# schematic.net
KiCad netlist of a schematic drawn in EAGLE
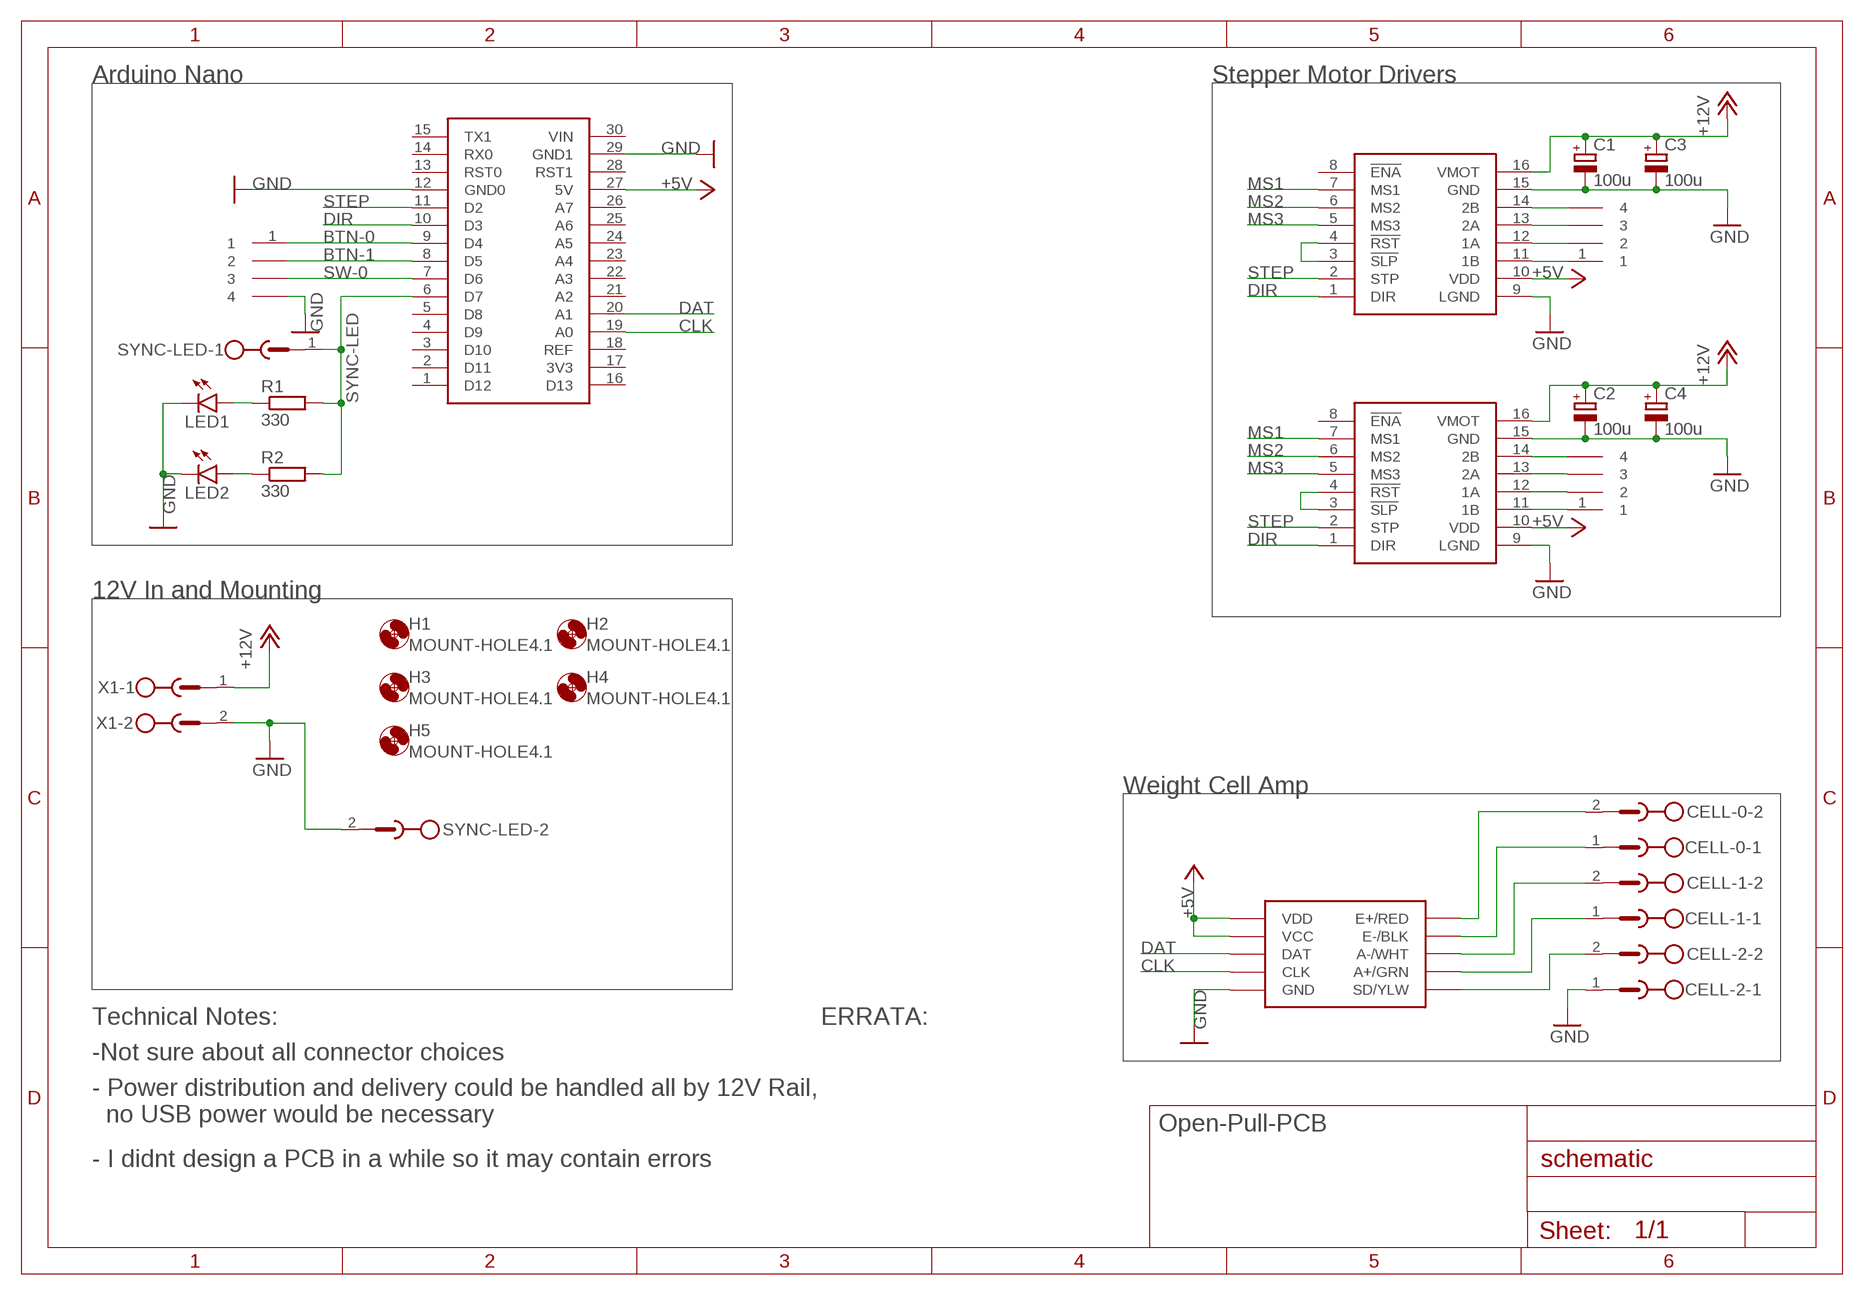
[diagram p0: schematic, sheet 1]

(export (version "E")
  (design (tool "Eeschema 10.0.6"))
  (components
    (comp (ref "C1")
      (value "100u")
      (footprint "eagle-import:3.5MM-CAP")
      (libsource (lib "eagle-import") (part "CPOL"))
    )
    (comp (ref "C2")
      (value "100u")
      (footprint "eagle-import:3.5MM-CAP")
      (libsource (lib "eagle-import") (part "CPOL"))
    )
    (comp (ref "C3")
      (value "100u")
      (footprint "eagle-import:CAPAE830X1050")
      (libsource (lib "eagle-import") (part "CPOLSMD-CAP"))
    )
    (comp (ref "C4")
      (value "100u")
      (footprint "eagle-import:CAPAE830X1050")
      (libsource (lib "eagle-import") (part "CPOLSMD-CAP"))
    )
    (comp (ref "CELL-0")
      (value "MSTBV2")
      (footprint "eagle-import:MSTBV2")
      (libsource (lib "eagle-import") (part "MSTBV2"))
    )
    (comp (ref "CELL-1")
      (value "MSTBV2")
      (footprint "eagle-import:MSTBV2")
      (libsource (lib "eagle-import") (part "MSTBV2"))
    )
    (comp (ref "CELL-2")
      (value "MSTBV2")
      (footprint "eagle-import:MSTBV2")
      (libsource (lib "eagle-import") (part "MSTBV2"))
    )
    (comp (ref "CON1")
      (value "CON-4GENERIC")
      (footprint "eagle-import:HDRV4W64P254_1X4_1016X508X838B")
      (libsource (lib "eagle-import") (part "CON-4GENERIC"))
    )
    (comp (ref "CON2")
      (value "CON-4GENERIC")
      (footprint "eagle-import:HDRV4W64P254_1X4_1016X508X838B")
      (libsource (lib "eagle-import") (part "CON-4GENERIC"))
    )
    (comp (ref "CON3")
      (value "CON-4GENERIC")
      (footprint "eagle-import:HDRV4W64P254_1X4_1016X508X838B")
      (libsource (lib "eagle-import") (part "CON-4GENERIC"))
    )
    (comp (ref "DRIVER1")
      (value "A4988-MODULE")
      (footprint "eagle-import:POLULU-A4988")
      (libsource (lib "eagle-import") (part "A4988-MODULE"))
    )
    (comp (ref "DRIVER2")
      (value "A4988-MODULE")
      (footprint "eagle-import:POLULU-A4988")
      (libsource (lib "eagle-import") (part "A4988-MODULE"))
    )
    (comp (ref "H1")
      (value "MOUNT-HOLE4.1")
      (footprint "eagle-import:4,1")
      (libsource (lib "eagle-import") (part "MOUNT-HOLE4.1"))
    )
    (comp (ref "H2")
      (value "MOUNT-HOLE4.1")
      (footprint "eagle-import:4,1")
      (libsource (lib "eagle-import") (part "MOUNT-HOLE4.1"))
    )
    (comp (ref "H3")
      (value "MOUNT-HOLE4.1")
      (footprint "eagle-import:4,1")
      (libsource (lib "eagle-import") (part "MOUNT-HOLE4.1"))
    )
    (comp (ref "H4")
      (value "MOUNT-HOLE4.1")
      (footprint "eagle-import:4,1")
      (libsource (lib "eagle-import") (part "MOUNT-HOLE4.1"))
    )
    (comp (ref "H5")
      (value "MOUNT-HOLE4.1")
      (footprint "eagle-import:4,1")
      (libsource (lib "eagle-import") (part "MOUNT-HOLE4.1"))
    )
    (comp (ref "LED1")
      (value "LEDCHIP-LED0805")
      (footprint "eagle-import:CHIP-LED0805")
      (libsource (lib "eagle-import") (part "LEDCHIP-LED0805"))
    )
    (comp (ref "LED2")
      (value "LED3MM")
      (footprint "eagle-import:LED3MM")
      (libsource (lib "eagle-import") (part "LED3MM"))
    )
    (comp (ref "MODULE1")
      (value "HX711-MODULE")
      (footprint "eagle-import:SPARKFUN-HX711")
      (libsource (lib "eagle-import") (part "HX711-MODULE"))
    )
    (comp (ref "NANO1")
      (value "ARDUINO-NANO")
      (footprint "eagle-import:ARDUINO-NANO")
      (libsource (lib "eagle-import") (part "ARDUINO-NANO"))
    )
    (comp (ref "R1")
      (value "330")
      (footprint "eagle-import:R0805")
      (libsource (lib "eagle-import") (part "R-EU_R0805"))
    )
    (comp (ref "R2")
      (value "330")
      (footprint "eagle-import:0207_2V")
      (libsource (lib "eagle-import") (part "R-EU_0207/2V"))
    )
    (comp (ref "SYNC-LED")
      (value "MSTBV2")
      (footprint "eagle-import:MSTBV2")
      (libsource (lib "eagle-import") (part "MSTBV2"))
    )
    (comp (ref "X1")
      (value "MSTBV2")
      (footprint "eagle-import:MSTBV2")
      (libsource (lib "eagle-import") (part "MSTBV2"))
    )
  )
  (nets
    (net (code "1") (name "+5V") (class "Default")
      (node (ref "DRIVER1") (pin "10") (pinfunction "VDD_10") (pintype "power_in"))
      (node (ref "DRIVER2") (pin "10") (pinfunction "VDD_10") (pintype "power_in"))
      (node (ref "MODULE1") (pin "VCC") (pinfunction "VCC_VCC") (pintype "power_in"))
      (node (ref "MODULE1") (pin "VDD") (pinfunction "VDD_VDD") (pintype "power_in"))
      (node (ref "NANO1") (pin "27") (pinfunction "5V_27") (pintype "power_in"))
    )
    (net (code "2") (name "+12V") (class "Default")
      (node (ref "C1") (pin "+") (pinfunction "+_+") (pintype "passive"))
      (node (ref "C2") (pin "+") (pinfunction "+_+") (pintype "passive"))
      (node (ref "C3") (pin "1") (pinfunction "+_1") (pintype "passive"))
      (node (ref "C4") (pin "1") (pinfunction "+_1") (pintype "passive"))
      (node (ref "DRIVER1") (pin "16") (pinfunction "VMOT_16") (pintype "power_in"))
      (node (ref "DRIVER2") (pin "16") (pinfunction "VMOT_16") (pintype "power_in"))
      (node (ref "X1") (pin "1") (pinfunction "SK_1") (pintype "passive"))
    )
    (net (code "3") (name "/3V3") (class "Default")
      (node (ref "NANO1") (pin "17") (pinfunction "3V3_17") (pintype "power_in"))
    )
    (net (code "4") (name "/BTN-0") (class "Default")
      (node (ref "CON3") (pin "1") (pinfunction "1_1") (pintype "bidirectional"))
      (node (ref "NANO1") (pin "9") (pinfunction "D4_9") (pintype "bidirectional"))
    )
    (net (code "5") (name "/BTN-1") (class "Default")
      (node (ref "CON3") (pin "2") (pinfunction "2_2") (pintype "bidirectional"))
      (node (ref "NANO1") (pin "8") (pinfunction "D5_8") (pintype "bidirectional"))
    )
    (net (code "6") (name "/CLK") (class "Default")
      (node (ref "MODULE1") (pin "CLK") (pinfunction "CLK_CLK") (pintype "bidirectional"))
      (node (ref "NANO1") (pin "19") (pinfunction "A0_19") (pintype "bidirectional"))
    )
    (net (code "7") (name "/DAT") (class "Default")
      (node (ref "MODULE1") (pin "DAT") (pinfunction "DAT_DAT") (pintype "bidirectional"))
      (node (ref "NANO1") (pin "20") (pinfunction "A1_20") (pintype "bidirectional"))
    )
    (net (code "8") (name "/DIR") (class "Default")
      (node (ref "DRIVER1") (pin "1") (pinfunction "DIR_1") (pintype "bidirectional"))
      (node (ref "DRIVER2") (pin "1") (pinfunction "DIR_1") (pintype "bidirectional"))
      (node (ref "NANO1") (pin "10") (pinfunction "D3_10") (pintype "bidirectional"))
    )
    (net (code "9") (name "/MS1") (class "Default")
      (node (ref "DRIVER1") (pin "7") (pinfunction "MS1_7") (pintype "bidirectional"))
      (node (ref "DRIVER2") (pin "7") (pinfunction "MS1_7") (pintype "bidirectional"))
    )
    (net (code "10") (name "/MS2") (class "Default")
      (node (ref "DRIVER1") (pin "6") (pinfunction "MS2_6") (pintype "bidirectional"))
      (node (ref "DRIVER2") (pin "6") (pinfunction "MS2_6") (pintype "bidirectional"))
    )
    (net (code "11") (name "/MS3") (class "Default")
      (node (ref "DRIVER1") (pin "5") (pinfunction "MS3_5") (pintype "bidirectional"))
      (node (ref "DRIVER2") (pin "5") (pinfunction "MS3_5") (pintype "bidirectional"))
    )
    (net (code "12") (name "/STEP") (class "Default")
      (node (ref "DRIVER1") (pin "2") (pinfunction "STP_2") (pintype "bidirectional"))
      (node (ref "DRIVER2") (pin "2") (pinfunction "STP_2") (pintype "bidirectional"))
      (node (ref "NANO1") (pin "11") (pinfunction "D2_11") (pintype "bidirectional"))
    )
    (net (code "13") (name "/SW-0") (class "Default")
      (node (ref "CON3") (pin "3") (pinfunction "3_3") (pintype "bidirectional"))
      (node (ref "NANO1") (pin "7") (pinfunction "D6_7") (pintype "bidirectional"))
    )
    (net (code "14") (name "/SYNC-LED") (class "Default")
      (node (ref "NANO1") (pin "6") (pinfunction "D7_6") (pintype "bidirectional"))
      (node (ref "R1") (pin "2") (pinfunction "2_2") (pintype "passive"))
      (node (ref "R2") (pin "2") (pinfunction "2_2") (pintype "passive"))
      (node (ref "SYNC-LED") (pin "1") (pinfunction "SK_1") (pintype "passive"))
    )
    (net (code "15") (name "/VIN") (class "Default")
      (node (ref "NANO1") (pin "30") (pinfunction "VIN_30") (pintype "power_in"))
    )
    (net (code "16") (name "GND") (class "Default")
      (node (ref "C1") (pin "-") (pinfunction "-_-") (pintype "passive"))
      (node (ref "C2") (pin "-") (pinfunction "-_-") (pintype "passive"))
      (node (ref "C3") (pin "2") (pinfunction "-_2") (pintype "passive"))
      (node (ref "C4") (pin "2") (pinfunction "-_2") (pintype "passive"))
      (node (ref "CELL-2") (pin "1") (pinfunction "SK_1") (pintype "passive"))
      (node (ref "CON3") (pin "4") (pinfunction "4_4") (pintype "bidirectional"))
      (node (ref "DRIVER1") (pin "15") (pinfunction "GND_15") (pintype "power_in"))
      (node (ref "DRIVER1") (pin "9") (pinfunction "LGND_9") (pintype "power_in"))
      (node (ref "DRIVER2") (pin "15") (pinfunction "GND_15") (pintype "power_in"))
      (node (ref "DRIVER2") (pin "9") (pinfunction "LGND_9") (pintype "power_in"))
      (node (ref "LED1") (pin "C") (pinfunction "C_C") (pintype "passive"))
      (node (ref "LED2") (pin "K") (pinfunction "C_K") (pintype "passive"))
      (node (ref "MODULE1") (pin "GND") (pinfunction "GND_GND") (pintype "power_in"))
      (node (ref "NANO1") (pin "12") (pinfunction "GND0_12") (pintype "power_in"))
      (node (ref "NANO1") (pin "29") (pinfunction "GND1_29") (pintype "power_in"))
      (node (ref "SYNC-LED") (pin "2") (pinfunction "SK_2") (pintype "passive"))
      (node (ref "X1") (pin "2") (pinfunction "SK_2") (pintype "passive"))
    )
    (net (code "17") (name "Net-(CELL-0A-SK)") (class "Default")
      (node (ref "CELL-0") (pin "1") (pinfunction "SK_1") (pintype "passive"))
      (node (ref "MODULE1") (pin "BLK") (pinfunction "E-/BLK_BLK") (pintype "bidirectional"))
    )
    (net (code "18") (name "Net-(CELL-0B-SK)") (class "Default")
      (node (ref "CELL-0") (pin "2") (pinfunction "SK_2") (pintype "passive"))
      (node (ref "MODULE1") (pin "RED") (pinfunction "E+/RED_RED") (pintype "bidirectional"))
    )
    (net (code "19") (name "Net-(CELL-1A-SK)") (class "Default")
      (node (ref "CELL-1") (pin "1") (pinfunction "SK_1") (pintype "passive"))
      (node (ref "MODULE1") (pin "GRN") (pinfunction "A+/GRN_GRN") (pintype "bidirectional"))
    )
    (net (code "20") (name "Net-(CELL-1B-SK)") (class "Default")
      (node (ref "CELL-1") (pin "2") (pinfunction "SK_2") (pintype "passive"))
      (node (ref "MODULE1") (pin "WHT") (pinfunction "A-/WHT_WHT") (pintype "bidirectional"))
    )
    (net (code "21") (name "Net-(CELL-2B-SK)") (class "Default")
      (node (ref "CELL-2") (pin "2") (pinfunction "SK_2") (pintype "passive"))
      (node (ref "MODULE1") (pin "YEL") (pinfunction "SD/YLW_YEL") (pintype "bidirectional"))
    )
    (net (code "22") (name "Net-(DRIVER1-1A)") (class "Default")
      (node (ref "CON1") (pin "2") (pinfunction "2_2") (pintype "bidirectional"))
      (node (ref "DRIVER1") (pin "12") (pinfunction "1A_12") (pintype "bidirectional"))
    )
    (net (code "23") (name "Net-(DRIVER1-1B)") (class "Default")
      (node (ref "CON1") (pin "1") (pinfunction "1_1") (pintype "bidirectional"))
      (node (ref "DRIVER1") (pin "11") (pinfunction "1B_11") (pintype "bidirectional"))
    )
    (net (code "24") (name "Net-(DRIVER1-2A)") (class "Default")
      (node (ref "CON1") (pin "3") (pinfunction "3_3") (pintype "bidirectional"))
      (node (ref "DRIVER1") (pin "13") (pinfunction "2A_13") (pintype "bidirectional"))
    )
    (net (code "25") (name "Net-(DRIVER1-2B)") (class "Default")
      (node (ref "CON1") (pin "4") (pinfunction "4_4") (pintype "bidirectional"))
      (node (ref "DRIVER1") (pin "14") (pinfunction "2B_14") (pintype "bidirectional"))
    )
    (net (code "26") (name "Net-(DRIVER1-~{RST})") (class "Default")
      (node (ref "DRIVER1") (pin "3") (pinfunction "~{SLP}_3") (pintype "bidirectional"))
      (node (ref "DRIVER1") (pin "4") (pinfunction "~{RST}_4") (pintype "bidirectional"))
    )
    (net (code "27") (name "Net-(DRIVER2-1A)") (class "Default")
      (node (ref "CON2") (pin "2") (pinfunction "2_2") (pintype "bidirectional"))
      (node (ref "DRIVER2") (pin "12") (pinfunction "1A_12") (pintype "bidirectional"))
    )
    (net (code "28") (name "Net-(DRIVER2-1B)") (class "Default")
      (node (ref "CON2") (pin "1") (pinfunction "1_1") (pintype "bidirectional"))
      (node (ref "DRIVER2") (pin "11") (pinfunction "1B_11") (pintype "bidirectional"))
    )
    (net (code "29") (name "Net-(DRIVER2-2A)") (class "Default")
      (node (ref "CON2") (pin "3") (pinfunction "3_3") (pintype "bidirectional"))
      (node (ref "DRIVER2") (pin "13") (pinfunction "2A_13") (pintype "bidirectional"))
    )
    (net (code "30") (name "Net-(DRIVER2-2B)") (class "Default")
      (node (ref "CON2") (pin "4") (pinfunction "4_4") (pintype "bidirectional"))
      (node (ref "DRIVER2") (pin "14") (pinfunction "2B_14") (pintype "bidirectional"))
    )
    (net (code "31") (name "Net-(DRIVER2-~{RST})") (class "Default")
      (node (ref "DRIVER2") (pin "3") (pinfunction "~{SLP}_3") (pintype "bidirectional"))
      (node (ref "DRIVER2") (pin "4") (pinfunction "~{RST}_4") (pintype "bidirectional"))
    )
    (net (code "32") (name "Net-(LED1-PadA)") (class "Default")
      (node (ref "LED1") (pin "A") (pinfunction "A_A") (pintype "passive"))
      (node (ref "R1") (pin "1") (pinfunction "1_1") (pintype "passive"))
    )
    (net (code "33") (name "Net-(LED2-PadA)") (class "Default")
      (node (ref "LED2") (pin "A") (pinfunction "A_A") (pintype "passive"))
      (node (ref "R2") (pin "1") (pinfunction "1_1") (pintype "passive"))
    )
    (net (code "34") (name "unconnected-(DRIVER1-~{ENA}-Pad8)") (class "Default")
      (node (ref "DRIVER1") (pin "8") (pinfunction "~{ENA}_8") (pintype "bidirectional"))
    )
    (net (code "35") (name "unconnected-(DRIVER2-~{ENA}-Pad8)") (class "Default")
      (node (ref "DRIVER2") (pin "8") (pinfunction "~{ENA}_8") (pintype "bidirectional"))
    )
    (net (code "36") (name "unconnected-(NANO1-A2-Pad21)") (class "Default")
      (node (ref "NANO1") (pin "21") (pinfunction "A2_21") (pintype "bidirectional"))
    )
    (net (code "37") (name "unconnected-(NANO1-A3-Pad22)") (class "Default")
      (node (ref "NANO1") (pin "22") (pinfunction "A3_22") (pintype "bidirectional"))
    )
    (net (code "38") (name "unconnected-(NANO1-A4-Pad23)") (class "Default")
      (node (ref "NANO1") (pin "23") (pinfunction "A4_23") (pintype "bidirectional"))
    )
    (net (code "39") (name "unconnected-(NANO1-A5-Pad24)") (class "Default")
      (node (ref "NANO1") (pin "24") (pinfunction "A5_24") (pintype "bidirectional"))
    )
    (net (code "40") (name "unconnected-(NANO1-A6-Pad25)") (class "Default")
      (node (ref "NANO1") (pin "25") (pinfunction "A6_25") (pintype "bidirectional"))
    )
    (net (code "41") (name "unconnected-(NANO1-A7-Pad26)") (class "Default")
      (node (ref "NANO1") (pin "26") (pinfunction "A7_26") (pintype "bidirectional"))
    )
    (net (code "42") (name "unconnected-(NANO1-D8-Pad5)") (class "Default")
      (node (ref "NANO1") (pin "5") (pinfunction "D8_5") (pintype "bidirectional"))
    )
    (net (code "43") (name "unconnected-(NANO1-D9-Pad4)") (class "Default")
      (node (ref "NANO1") (pin "4") (pinfunction "D9_4") (pintype "bidirectional"))
    )
    (net (code "44") (name "unconnected-(NANO1-D10-Pad3)") (class "Default")
      (node (ref "NANO1") (pin "3") (pinfunction "D10_3") (pintype "bidirectional"))
    )
    (net (code "45") (name "unconnected-(NANO1-D11-Pad2)") (class "Default")
      (node (ref "NANO1") (pin "2") (pinfunction "D11_2") (pintype "bidirectional"))
    )
    (net (code "46") (name "unconnected-(NANO1-D12-Pad1)") (class "Default")
      (node (ref "NANO1") (pin "1") (pinfunction "D12_1") (pintype "bidirectional"))
    )
    (net (code "47") (name "unconnected-(NANO1-D13-Pad16)") (class "Default")
      (node (ref "NANO1") (pin "16") (pinfunction "D13_16") (pintype "bidirectional"))
    )
    (net (code "48") (name "unconnected-(NANO1-REF-Pad18)") (class "Default")
      (node (ref "NANO1") (pin "18") (pinfunction "REF_18") (pintype "bidirectional"))
    )
    (net (code "49") (name "unconnected-(NANO1-RST0-Pad13)") (class "Default")
      (node (ref "NANO1") (pin "13") (pinfunction "RST0_13") (pintype "bidirectional"))
    )
    (net (code "50") (name "unconnected-(NANO1-RST1-Pad28)") (class "Default")
      (node (ref "NANO1") (pin "28") (pinfunction "RST1_28") (pintype "bidirectional"))
    )
    (net (code "51") (name "unconnected-(NANO1-RX0-Pad14)") (class "Default")
      (node (ref "NANO1") (pin "14") (pinfunction "RX0_14") (pintype "bidirectional"))
    )
    (net (code "52") (name "unconnected-(NANO1-TX1-Pad15)") (class "Default")
      (node (ref "NANO1") (pin "15") (pinfunction "TX1_15") (pintype "bidirectional"))
    )
  )
)
